# fretscanner-untangle.net
KiCad netlist of a schematic drawn in EAGLE
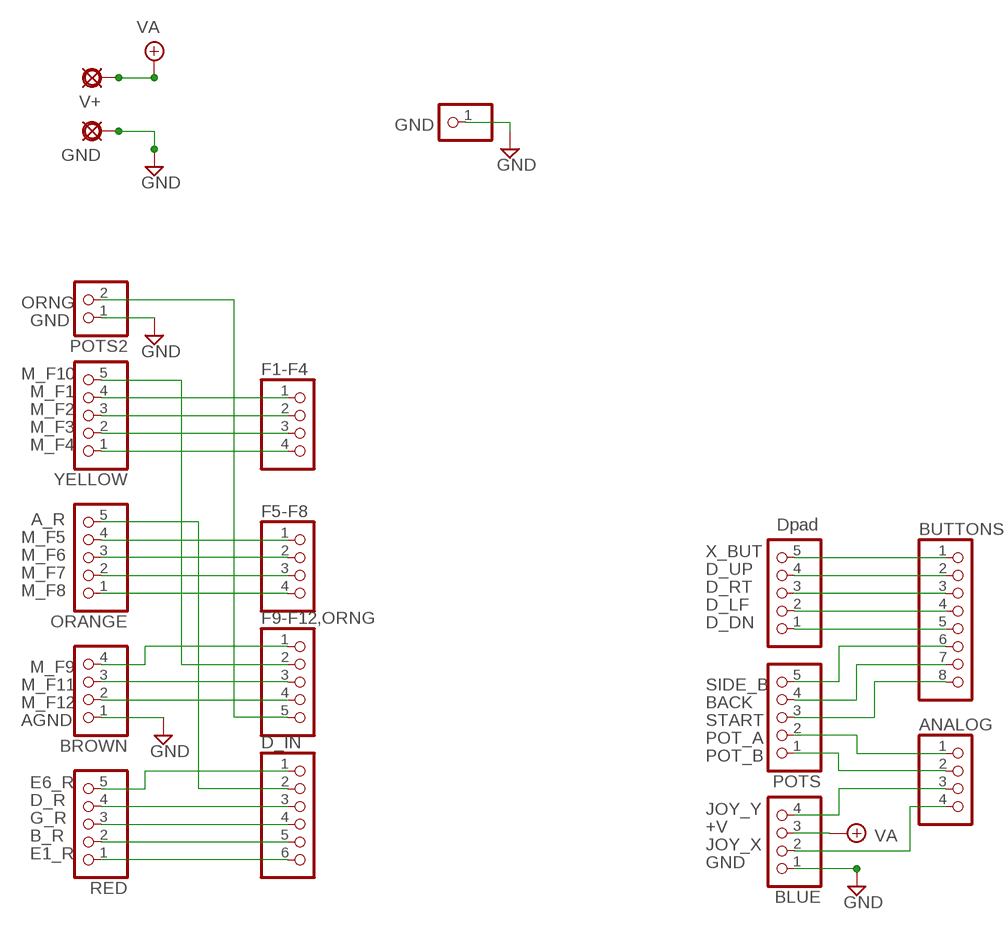
[diagram p0: schematic, sheet 1]

(export (version "E")
  (design (tool "Eeschema 10.0.6"))
  (components
    (comp (ref "ANALOG")
      (value "PINHD-1X4")
      (footprint "eagle-import:1X04")
      (libsource (lib "eagle-import") (part "PINHD-1X4"))
    )
    (comp (ref "BLUE")
      (value "PINHD-1X4")
      (footprint "eagle-import:1X04")
      (libsource (lib "eagle-import") (part "PINHD-1X4"))
    )
    (comp (ref "BROWN")
      (value "PINHD-1X4")
      (footprint "eagle-import:1X04")
      (libsource (lib "eagle-import") (part "PINHD-1X4"))
    )
    (comp (ref "BUTTONS")
      (value "PINHD-1X8")
      (footprint "eagle-import:1X08")
      (libsource (lib "eagle-import") (part "PINHD-1X8"))
    )
    (comp (ref "DPAD")
      (value "PINHD-1X5")
      (footprint "eagle-import:1X05")
      (libsource (lib "eagle-import") (part "PINHD-1X5"))
    )
    (comp (ref "DPAD2")
      (value "PINHD-1X1")
      (footprint "eagle-import:1X01")
      (libsource (lib "eagle-import") (part "PINHD-1X1"))
    )
    (comp (ref "D_IN")
      (value "PINHD-1X6")
      (footprint "eagle-import:1X06")
      (libsource (lib "eagle-import") (part "PINHD-1X6"))
    )
    (comp (ref "F1-F4")
      (value "PINHD-1X4")
      (footprint "eagle-import:1X04")
      (libsource (lib "eagle-import") (part "PINHD-1X4"))
    )
    (comp (ref "F5-F8")
      (value "PINHD-1X4")
      (footprint "eagle-import:1X04")
      (libsource (lib "eagle-import") (part "PINHD-1X4"))
    )
    (comp (ref "F9-F12,ORNG")
      (value "PINHD-1X5")
      (footprint "eagle-import:1X05")
      (libsource (lib "eagle-import") (part "PINHD-1X5"))
    )
    (comp (ref "GND")
      (value "PADL")
      (footprint "eagle-import:LONG")
      (libsource (lib "eagle-import") (part "PADL"))
    )
    (comp (ref "ORANGE")
      (value "PINHD-1X5")
      (footprint "eagle-import:1X05")
      (libsource (lib "eagle-import") (part "PINHD-1X5"))
    )
    (comp (ref "POTS")
      (value "PINHD-1X5")
      (footprint "eagle-import:1X05")
      (libsource (lib "eagle-import") (part "PINHD-1X5"))
    )
    (comp (ref "POTS2")
      (value "PINHD-1X2")
      (footprint "eagle-import:1X02")
      (libsource (lib "eagle-import") (part "PINHD-1X2"))
    )
    (comp (ref "RED")
      (value "PINHD-1X5")
      (footprint "eagle-import:1X05")
      (libsource (lib "eagle-import") (part "PINHD-1X5"))
    )
    (comp (ref "V+")
      (value "PADL")
      (footprint "eagle-import:LONG")
      (libsource (lib "eagle-import") (part "PADL"))
    )
    (comp (ref "YELLOW")
      (value "PINHD-1X5")
      (footprint "eagle-import:1X05")
      (libsource (lib "eagle-import") (part "PINHD-1X5"))
    )
  )
  (nets
    (net (code "1") (name "GND") (class "Default")
      (node (ref "BLUE") (pin "1") (pinfunction "1_1") (pintype "passive"))
      (node (ref "BROWN") (pin "1") (pinfunction "1_1") (pintype "passive"))
      (node (ref "DPAD2") (pin "1") (pinfunction "1_1") (pintype "passive"))
      (node (ref "GND") (pin "1") (pinfunction "PAD_1") (pintype "passive"))
      (node (ref "POTS2") (pin "1") (pinfunction "1_1") (pintype "passive"))
    )
    (net (code "2") (name "Net-(ANALOG-Pad1)") (class "Default")
      (node (ref "ANALOG") (pin "1") (pinfunction "1_1") (pintype "passive"))
      (node (ref "POTS") (pin "2") (pinfunction "2_2") (pintype "passive"))
    )
    (net (code "3") (name "Net-(ANALOG-Pad2)") (class "Default")
      (node (ref "ANALOG") (pin "2") (pinfunction "2_2") (pintype "passive"))
      (node (ref "POTS") (pin "1") (pinfunction "1_1") (pintype "passive"))
    )
    (net (code "4") (name "Net-(ANALOG-Pad3)") (class "Default")
      (node (ref "ANALOG") (pin "3") (pinfunction "3_3") (pintype "passive"))
      (node (ref "BLUE") (pin "4") (pinfunction "4_4") (pintype "passive"))
    )
    (net (code "5") (name "Net-(ANALOG-Pad4)") (class "Default")
      (node (ref "ANALOG") (pin "4") (pinfunction "4_4") (pintype "passive"))
      (node (ref "BLUE") (pin "2") (pinfunction "2_2") (pintype "passive"))
    )
    (net (code "6") (name "Net-(BROWN-Pad2)") (class "Default")
      (node (ref "BROWN") (pin "2") (pinfunction "2_2") (pintype "passive"))
      (node (ref "F9-F12,ORNG") (pin "4") (pinfunction "4_4") (pintype "passive"))
    )
    (net (code "7") (name "Net-(BROWN-Pad3)") (class "Default")
      (node (ref "BROWN") (pin "3") (pinfunction "3_3") (pintype "passive"))
      (node (ref "F9-F12,ORNG") (pin "3") (pinfunction "3_3") (pintype "passive"))
    )
    (net (code "8") (name "Net-(BROWN-Pad4)") (class "Default")
      (node (ref "BROWN") (pin "4") (pinfunction "4_4") (pintype "passive"))
      (node (ref "F9-F12,ORNG") (pin "1") (pinfunction "1_1") (pintype "passive"))
    )
    (net (code "9") (name "Net-(BUTTONS-Pad1)") (class "Default")
      (node (ref "BUTTONS") (pin "1") (pinfunction "1_1") (pintype "passive"))
      (node (ref "DPAD") (pin "5") (pinfunction "5_5") (pintype "passive"))
    )
    (net (code "10") (name "Net-(BUTTONS-Pad2)") (class "Default")
      (node (ref "BUTTONS") (pin "2") (pinfunction "2_2") (pintype "passive"))
      (node (ref "DPAD") (pin "4") (pinfunction "4_4") (pintype "passive"))
    )
    (net (code "11") (name "Net-(BUTTONS-Pad3)") (class "Default")
      (node (ref "BUTTONS") (pin "3") (pinfunction "3_3") (pintype "passive"))
      (node (ref "DPAD") (pin "3") (pinfunction "3_3") (pintype "passive"))
    )
    (net (code "12") (name "Net-(BUTTONS-Pad4)") (class "Default")
      (node (ref "BUTTONS") (pin "4") (pinfunction "4_4") (pintype "passive"))
      (node (ref "DPAD") (pin "2") (pinfunction "2_2") (pintype "passive"))
    )
    (net (code "13") (name "Net-(BUTTONS-Pad5)") (class "Default")
      (node (ref "BUTTONS") (pin "5") (pinfunction "5_5") (pintype "passive"))
      (node (ref "DPAD") (pin "1") (pinfunction "1_1") (pintype "passive"))
    )
    (net (code "14") (name "Net-(BUTTONS-Pad6)") (class "Default")
      (node (ref "BUTTONS") (pin "6") (pinfunction "6_6") (pintype "passive"))
      (node (ref "POTS") (pin "5") (pinfunction "5_5") (pintype "passive"))
    )
    (net (code "15") (name "Net-(BUTTONS-Pad7)") (class "Default")
      (node (ref "BUTTONS") (pin "7") (pinfunction "7_7") (pintype "passive"))
      (node (ref "POTS") (pin "4") (pinfunction "4_4") (pintype "passive"))
    )
    (net (code "16") (name "Net-(BUTTONS-Pad8)") (class "Default")
      (node (ref "BUTTONS") (pin "8") (pinfunction "8_8") (pintype "passive"))
      (node (ref "POTS") (pin "3") (pinfunction "3_3") (pintype "passive"))
    )
    (net (code "17") (name "Net-(D_IN-Pad1)") (class "Default")
      (node (ref "D_IN") (pin "1") (pinfunction "1_1") (pintype "passive"))
      (node (ref "RED") (pin "5") (pinfunction "5_5") (pintype "passive"))
    )
    (net (code "18") (name "Net-(D_IN-Pad2)") (class "Default")
      (node (ref "D_IN") (pin "2") (pinfunction "2_2") (pintype "passive"))
      (node (ref "ORANGE") (pin "5") (pinfunction "5_5") (pintype "passive"))
    )
    (net (code "19") (name "Net-(D_IN-Pad3)") (class "Default")
      (node (ref "D_IN") (pin "3") (pinfunction "3_3") (pintype "passive"))
      (node (ref "RED") (pin "4") (pinfunction "4_4") (pintype "passive"))
    )
    (net (code "20") (name "Net-(D_IN-Pad4)") (class "Default")
      (node (ref "D_IN") (pin "4") (pinfunction "4_4") (pintype "passive"))
      (node (ref "RED") (pin "3") (pinfunction "3_3") (pintype "passive"))
    )
    (net (code "21") (name "Net-(D_IN-Pad5)") (class "Default")
      (node (ref "D_IN") (pin "5") (pinfunction "5_5") (pintype "passive"))
      (node (ref "RED") (pin "2") (pinfunction "2_2") (pintype "passive"))
    )
    (net (code "22") (name "Net-(D_IN-Pad6)") (class "Default")
      (node (ref "D_IN") (pin "6") (pinfunction "6_6") (pintype "passive"))
      (node (ref "RED") (pin "1") (pinfunction "1_1") (pintype "passive"))
    )
    (net (code "23") (name "Net-(F1-F4-Pad1)") (class "Default")
      (node (ref "F1-F4") (pin "1") (pinfunction "1_1") (pintype "passive"))
      (node (ref "YELLOW") (pin "4") (pinfunction "4_4") (pintype "passive"))
    )
    (net (code "24") (name "Net-(F1-F4-Pad2)") (class "Default")
      (node (ref "F1-F4") (pin "2") (pinfunction "2_2") (pintype "passive"))
      (node (ref "YELLOW") (pin "3") (pinfunction "3_3") (pintype "passive"))
    )
    (net (code "25") (name "Net-(F1-F4-Pad3)") (class "Default")
      (node (ref "F1-F4") (pin "3") (pinfunction "3_3") (pintype "passive"))
      (node (ref "YELLOW") (pin "2") (pinfunction "2_2") (pintype "passive"))
    )
    (net (code "26") (name "Net-(F1-F4-Pad4)") (class "Default")
      (node (ref "F1-F4") (pin "4") (pinfunction "4_4") (pintype "passive"))
      (node (ref "YELLOW") (pin "1") (pinfunction "1_1") (pintype "passive"))
    )
    (net (code "27") (name "Net-(F5-F8-Pad1)") (class "Default")
      (node (ref "F5-F8") (pin "1") (pinfunction "1_1") (pintype "passive"))
      (node (ref "ORANGE") (pin "4") (pinfunction "4_4") (pintype "passive"))
    )
    (net (code "28") (name "Net-(F5-F8-Pad2)") (class "Default")
      (node (ref "F5-F8") (pin "2") (pinfunction "2_2") (pintype "passive"))
      (node (ref "ORANGE") (pin "3") (pinfunction "3_3") (pintype "passive"))
    )
    (net (code "29") (name "Net-(F5-F8-Pad3)") (class "Default")
      (node (ref "F5-F8") (pin "3") (pinfunction "3_3") (pintype "passive"))
      (node (ref "ORANGE") (pin "2") (pinfunction "2_2") (pintype "passive"))
    )
    (net (code "30") (name "Net-(F5-F8-Pad4)") (class "Default")
      (node (ref "F5-F8") (pin "4") (pinfunction "4_4") (pintype "passive"))
      (node (ref "ORANGE") (pin "1") (pinfunction "1_1") (pintype "passive"))
    )
    (net (code "31") (name "Net-(F9-F12,ORNG-Pad2)") (class "Default")
      (node (ref "F9-F12,ORNG") (pin "2") (pinfunction "2_2") (pintype "passive"))
      (node (ref "YELLOW") (pin "5") (pinfunction "5_5") (pintype "passive"))
    )
    (net (code "32") (name "Net-(F9-F12,ORNG-Pad5)") (class "Default")
      (node (ref "F9-F12,ORNG") (pin "5") (pinfunction "5_5") (pintype "passive"))
      (node (ref "POTS2") (pin "2") (pinfunction "2_2") (pintype "passive"))
    )
    (net (code "33") (name "VA") (class "Default")
      (node (ref "BLUE") (pin "3") (pinfunction "3_3") (pintype "passive"))
      (node (ref "V+") (pin "1") (pinfunction "PAD_1") (pintype "passive"))
    )
  )
)
